# VBATTPrimary.net
KiCad netlist of a schematic drawn in Altium Designer
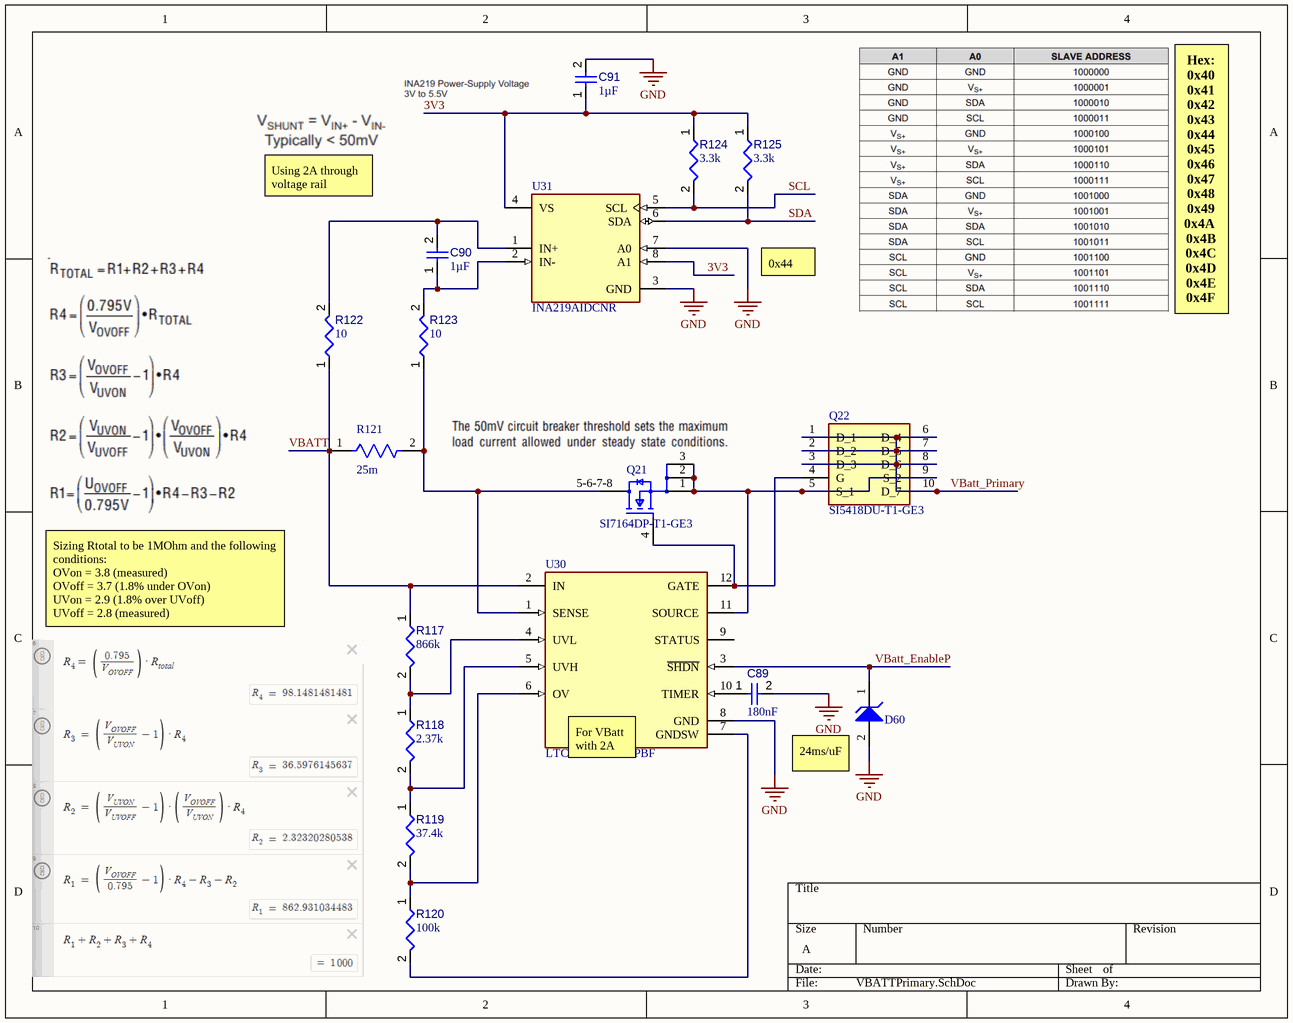
[diagram p0: VBATTPrimary.SchDoc]

(export (version "E")
  (design (tool "Eeschema 10.0.6"))
  (components
    (comp (ref "C89")
      (value "180nF")
      (footprint "FP-C0805C-DN-IPC_A")
      (fields (field (name "Comment") "C0805C184K5RACTU"))
      (libsource (lib "UGA SSRL Hardware Team") (part "CAP-NP-2"))
    )
    (comp (ref "C90")
      (value "1µF")
      (footprint "CAPC1608X90X40LL10T20")
      (description "Chip Capacitor, 1 uF, +/- 10%, 25 V, 0603 (1608 Metric)")
      (fields (field (name "TOLERANCE") "10%") (field (name "Comment") "Capacitor 1 uF +/- 10% 25 V 0603"))
      (libsource (lib "UGA SSRL Hardware Team") (part "CAP-NP-2"))
    )
    (comp (ref "C91")
      (value "1µF")
      (footprint "CAPC1608X90X35ML15T15")
      (description "Chip Capacitor, 1 uF, +/- 10%, 16 V, 0603 (1608 Metric)")
      (fields (field (name "TOLERANCE") "10%") (field (name "Comment") "Capacitor 1uF +/- 10% 16V 0603"))
      (libsource (lib "UGA SSRL Hardware Team") (part "CAP-NP-2"))
    )
    (comp (ref "D60")
      (value "MM3Z3V6T1G")
      (footprint "ONSC-SOD-323-2-477-02_V")
      (description "Zener Voltage Regulator, 300 mW, 2-Pin SOD-323, Pb-Free, Tape and Reel")
      (fields (field (name "MANUFACTURER") "On Semiconductor"))
      (libsource (lib "Altium Content Vault") (part "ONSC-K1A2-2"))
    )
    (comp (ref "Q21")
      (value "SI7164DP-T1-GE3")
      (footprint "Vishay_S17-0173-SINGLE_MFG")
      (libsource (lib "UGA SSRL Hardware Team") (part "SI7164DP-T1-GE3"))
    )
    (comp (ref "Q22")
      (value "SI5418DU-T1-GE3")
      (footprint "SI5418DU-T1-GE3-Footprint-1")
      (libsource (lib "UGA SSRL Hardware Team") (part "SI5418DU-T1-GE3-Symbol-1"))
    )
    (comp (ref "R117")
      (value "866k")
      (footprint "RESC0603X26X15NL03T05")
      (description "Fixed Resistor, Metal Glaze/thick Film, 0.05W, 866000ohm, 25V, 1% +/-Tol, -200,200ppm/Cel, 0201")
      (fields (field (name "TOLERANCE") "1%") (field (name "POWER") "50mW"))
      (libsource (lib "UGA SSRL Hardware Team") (part "RES-2"))
    )
    (comp (ref "R118")
      (value "2.37k")
      (footprint "RESC0402(1005)_L")
      (description "2K37 0.063W 1% 0402 (1005 Metric)  SMD")
      (fields (field (name "TOLERANCE") "1%") (field (name "POWER") "63mW"))
      (libsource (lib "UGA SSRL Hardware Team") (part "2D37KR2F"))
    )
    (comp (ref "R119")
      (value "37.4k")
      (footprint "FP-CR0603-IPC_A")
      (fields
        (field (name "POWER") "100mW")
        (field (name "TOLERANCE") "1%")
        (field (name "Comment") "CR0603-FX-3742ELF")
      )
      (libsource (lib "UGA SSRL Hardware Team") (part "RES-2"))
    )
    (comp (ref "R120")
      (value "100k")
      (footprint "RESC1005X40X25ML05T05")
      (description "Chip Resistor, 100 KOhm, +/- 1%, 0.1 W, -55 to 155 degC, 0402 (1005 Metric)")
      (fields (field (name "POWER") "100mW") (field (name "TOLERANCE") "1%"))
      (libsource (lib "UGA SSRL Hardware Team") (part "RES-2"))
    )
    (comp (ref "R121")
      (value "CSR1206FK25L0")
      (footprint "FP-CSR1206-IPC_C")
      (description "General Purpose Thick Film Chip Resistor, 1206, 25mΩ, 1%, 0.5W")
      (fields (field (name "RESISTANCE") "25m") (field (name "TOLERANCE") "1%"))
      (libsource (lib "Altium Content Vault") (part "1029c3af85768c4190bb7ad29bc67b5"))
    )
    (comp (ref "R122")
      (value "10")
      (footprint "RESC0402(1005)_L")
      (description "Chip Resistor, 10 Ohms, +/-1 %, 63 mW, -55 to 155 degC, 0402")
      (fields (field (name "TOLERANCE") "1%") (field (name "POWER") "63mW"))
      (libsource (lib "UGA SSRL Hardware Team") (part "RES-2"))
    )
    (comp (ref "R123")
      (value "10")
      (footprint "RESC0402(1005)_L")
      (description "Chip Resistor, 10 Ohms, +/-1 %, 63 mW, -55 to 155 degC, 0402")
      (fields (field (name "TOLERANCE") "1%") (field (name "POWER") "63mW"))
      (libsource (lib "UGA SSRL Hardware Team") (part "RES-2"))
    )
    (comp (ref "R124")
      (value "3.3k")
      (footprint "FP-CRCW1210-e3-IPC_C")
      (fields
        (field (name "TOLERANCE") "5%")
        (field (name "POWER") "500mW")
        (field (name "Comment") "CRCW12103K30JNEA")
      )
      (libsource (lib "UGA SSRL Hardware Team") (part "RES-2"))
    )
    (comp (ref "R125")
      (value "3.3k")
      (footprint "FP-CRCW1210-e3-IPC_C")
      (fields
        (field (name "TOLERANCE") "5%")
        (field (name "POWER") "500mW")
        (field (name "Comment") "CRCW12103K30JNEA")
      )
      (libsource (lib "UGA SSRL Hardware Team") (part "RES-2"))
    )
    (comp (ref "U30")
      (value "LTC4231HMS-1#PBF")
      (footprint "FP-MS-12-05-08-1668-MFG")
      (description "IC HOT SWAP CTRLR GP 12MSOP")
      (libsource (lib "Altium Content Vault") (part "22a006f8750c3b6cd4295fbd2c2f62c"))
    )
    (comp (ref "U31")
      (value "INA219AIDCNR")
      (footprint "FP-DCN0008A-IPC_A")
      (description "Power Supply Support Circuit, Fixed, 2 Channel, 2V, PDSO8")
      (libsource (lib "UGA SSRL Hardware Team") (part "e16934b8ef90d0e345b266f0ae9cd81"))
    )
  )
  (nets
    (net (code "1") (name "/3V3") (class "Default")
      (node (ref "C91") (pin "1") (pinfunction "1_1") (pintype "passive"))
      (node (ref "R124") (pin "1") (pinfunction "1_1") (pintype "passive"))
      (node (ref "R125") (pin "1") (pinfunction "1_1") (pintype "passive"))
      (node (ref "U31") (pin "4") (pinfunction "VS_4") (pintype "power_in"))
      (node (ref "U31") (pin "8") (pinfunction "A1_8") (pintype "input"))
    )
    (net (code "2") (name "/SCL") (class "Default")
      (node (ref "R124") (pin "2") (pinfunction "2_2") (pintype "passive"))
      (node (ref "U31") (pin "5") (pinfunction "SCL_5") (pintype "input"))
    )
    (net (code "3") (name "/SDA") (class "Default")
      (node (ref "R125") (pin "2") (pinfunction "2_2") (pintype "passive"))
      (node (ref "U31") (pin "6") (pinfunction "SDA_6") (pintype "bidirectional"))
    )
    (net (code "4") (name "/VBATT") (class "Default")
      (node (ref "R117") (pin "1") (pinfunction "1_1") (pintype "passive"))
      (node (ref "R121") (pin "1") (pinfunction "1_1") (pintype "passive"))
      (node (ref "R122") (pin "1") (pinfunction "1_1") (pintype "passive"))
      (node (ref "U30") (pin "2") (pinfunction "IN_2") (pintype "power_in"))
    )
    (net (code "5") (name "/VBatt_EnableP") (class "Default")
      (node (ref "D60") (pin "1") (pinfunction "K_1") (pintype "passive"))
      (node (ref "U30") (pin "3") (pinfunction "~{SHDN}_3") (pintype "input"))
    )
    (net (code "6") (name "/VBatt_Primary") (class "Default")
      (node (ref "Q22") (pin "1") (pinfunction "D_1_1") (pintype "passive"))
      (node (ref "Q22") (pin "10") (pinfunction "D_7_10") (pintype "passive"))
      (node (ref "Q22") (pin "2") (pinfunction "D_2_2") (pintype "passive"))
      (node (ref "Q22") (pin "3") (pinfunction "D_3_3") (pintype "passive"))
      (node (ref "Q22") (pin "6") (pinfunction "D_4_6") (pintype "passive"))
      (node (ref "Q22") (pin "7") (pinfunction "D_5_7") (pintype "passive"))
      (node (ref "Q22") (pin "8") (pinfunction "D_6_8") (pintype "passive"))
    )
    (net (code "7") (name "GND") (class "Default")
      (node (ref "C89") (pin "2") (pinfunction "2_2") (pintype "passive"))
      (node (ref "C91") (pin "2") (pinfunction "2_2") (pintype "passive"))
      (node (ref "D60") (pin "2") (pinfunction "A_2") (pintype "passive"))
      (node (ref "U30") (pin "8") (pinfunction "GND_8") (pintype "power_in"))
      (node (ref "U31") (pin "3") (pinfunction "GND_3") (pintype "power_in"))
      (node (ref "U31") (pin "7") (pinfunction "A0_7") (pintype "input"))
    )
    (net (code "8") (name "Net-(Q21-D)") (class "Default")
      (node (ref "Q21") (pin "5-6-7-8") (pinfunction "D_5-6-7-8") (pintype "passive"))
      (node (ref "R121") (pin "2") (pinfunction "2_2") (pintype "passive"))
      (node (ref "R123") (pin "1") (pinfunction "1_1") (pintype "passive"))
      (node (ref "U30") (pin "1") (pinfunction "SENSE_1") (pintype "input"))
    )
    (net (code "9") (name "Net-(Q21-G)") (class "Default")
      (node (ref "Q21") (pin "4") (pinfunction "G_4") (pintype "passive"))
      (node (ref "Q22") (pin "4") (pinfunction "G_4") (pintype "passive"))
      (node (ref "U30") (pin "12") (pinfunction "GATE_12") (pintype "passive"))
    )
    (net (code "10") (name "Net-(Q22-S_1)") (class "Default")
      (node (ref "Q21") (pin "1") (pinfunction "S_1") (pintype "passive"))
      (node (ref "Q21") (pin "2") (pinfunction "S_2") (pintype "passive"))
      (node (ref "Q21") (pin "3") (pinfunction "S_3") (pintype "passive"))
      (node (ref "Q22") (pin "5") (pinfunction "S_1_5") (pintype "passive"))
      (node (ref "Q22") (pin "9") (pinfunction "S_2_9") (pintype "passive"))
      (node (ref "U30") (pin "11") (pinfunction "SOURCE_11") (pintype "passive"))
    )
    (net (code "11") (name "Net-(U30-GNDSW)") (class "Default")
      (node (ref "R120") (pin "2") (pinfunction "2_2") (pintype "passive"))
      (node (ref "U30") (pin "7") (pinfunction "GNDSW_7") (pintype "power_in"))
    )
    (net (code "12") (name "Net-(U30-OV)") (class "Default")
      (node (ref "R119") (pin "2") (pinfunction "2_2") (pintype "passive"))
      (node (ref "R120") (pin "1") (pinfunction "1_1") (pintype "passive"))
      (node (ref "U30") (pin "6") (pinfunction "OV_6") (pintype "input"))
    )
    (net (code "13") (name "Net-(U30-TIMER)") (class "Default")
      (node (ref "C89") (pin "1") (pinfunction "1_1") (pintype "passive"))
      (node (ref "U30") (pin "10") (pinfunction "TIMER_10") (pintype "input"))
    )
    (net (code "14") (name "Net-(U30-UVH)") (class "Default")
      (node (ref "R118") (pin "2") (pinfunction "2_2") (pintype "passive"))
      (node (ref "R119") (pin "1") (pinfunction "1_1") (pintype "passive"))
      (node (ref "U30") (pin "5") (pinfunction "UVH_5") (pintype "input"))
    )
    (net (code "15") (name "Net-(U30-UVL)") (class "Default")
      (node (ref "R117") (pin "2") (pinfunction "2_2") (pintype "passive"))
      (node (ref "R118") (pin "1") (pinfunction "1_1") (pintype "passive"))
      (node (ref "U30") (pin "4") (pinfunction "UVL_4") (pintype "input"))
    )
    (net (code "16") (name "Net-(U31-IN+)") (class "Default")
      (node (ref "C90") (pin "2") (pinfunction "2_2") (pintype "passive"))
      (node (ref "R122") (pin "2") (pinfunction "2_2") (pintype "passive"))
      (node (ref "U31") (pin "1") (pinfunction "IN+_1") (pintype "passive"))
    )
    (net (code "17") (name "Net-(U31-IN-)") (class "Default")
      (node (ref "C90") (pin "1") (pinfunction "1_1") (pintype "passive"))
      (node (ref "R123") (pin "2") (pinfunction "2_2") (pintype "passive"))
      (node (ref "U31") (pin "2") (pinfunction "IN-_2") (pintype "input"))
    )
    (net (code "18") (name "unconnected-(U30-STATUS-Pad9)") (class "Default")
      (node (ref "U30") (pin "9") (pinfunction "STATUS_9") (pintype "open_collector"))
    )
  )
)
